# os33_master.net
KiCad netlist of a schematic drawn in EAGLE
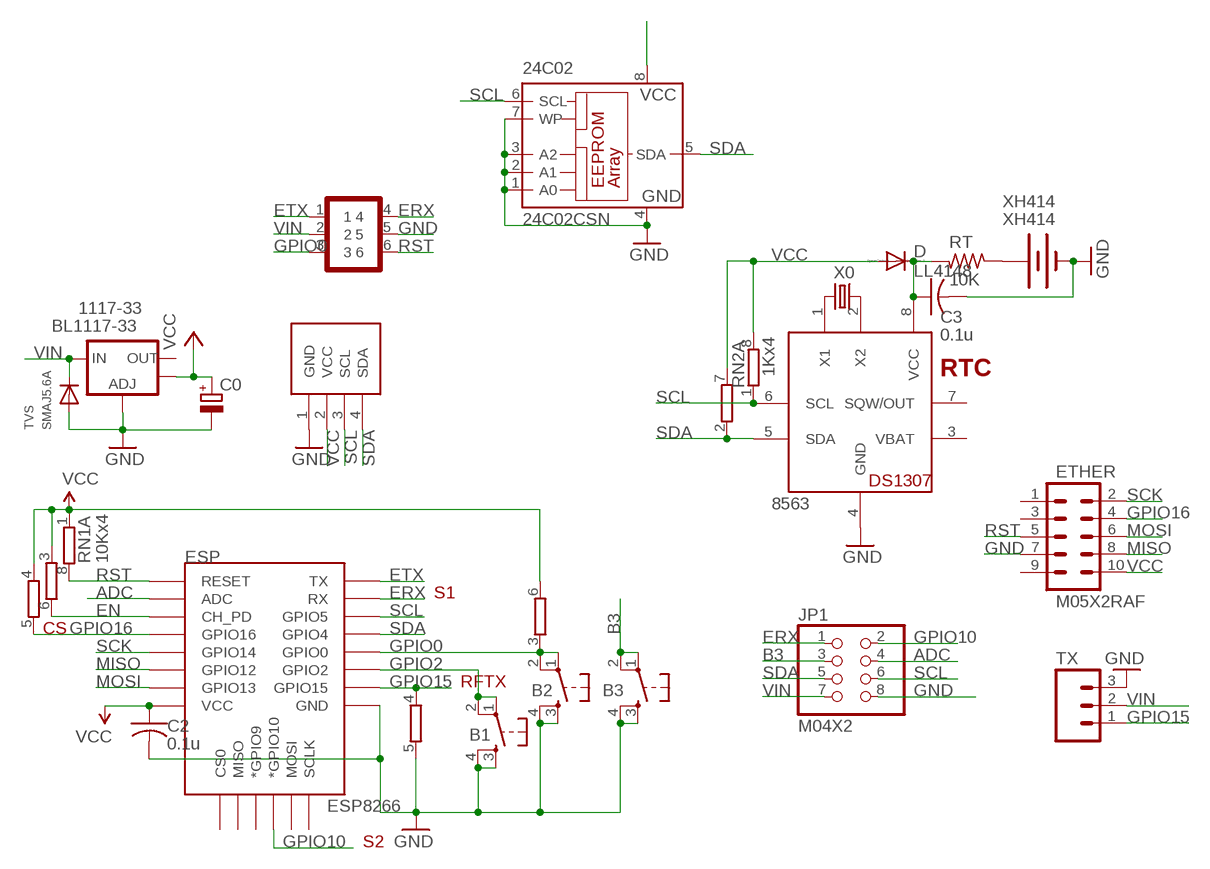
[diagram p0: schematic, sheet 1]

(export (version "E")
  (design (tool "Eeschema 10.0.6"))
  (components
    (comp (ref "24C02")
      (value "24C02CSN")
      (footprint "eagle-import:SO-08")
      (fields (field (name "MF") "MICROCHIP") (field (name "MPN") "24C02C/SN"))
      (libsource (lib "eagle-import") (part "24CSN02C"))
    )
    (comp (ref "1117-33")
      (value "BL1117-33")
      (footprint "eagle-import:SOT223")
      (libsource (lib "eagle-import") (part "V_REG_LM1117SOT223"))
    )
    (comp (ref "8563")
      (value "PCF8563")
      (footprint "eagle-import:SO08")
      (libsource (lib "eagle-import") (part "DS1307SOIC"))
    )
    (comp (ref "B1")
      (value "SPST_TACTEVQQ2")
      (footprint "eagle-import:EVQ-Q2")
      (libsource (lib "eagle-import") (part "SPST_TACTEVQQ2"))
    )
    (comp (ref "B2")
      (value "SPST_TACTEVQQ2")
      (footprint "eagle-import:EVQ-Q2")
      (libsource (lib "eagle-import") (part "SPST_TACTEVQQ2"))
    )
    (comp (ref "B3")
      (value "SPST_TACTEVQQ2")
      (footprint "eagle-import:EVQ-Q2")
      (libsource (lib "eagle-import") (part "SPST_TACTEVQQ2"))
    )
    (comp (ref "C0")
      (value "CPOL-EUC")
      (footprint "eagle-import:PANASONIC_C")
      (libsource (lib "eagle-import") (part "CPOL-EUC"))
    )
    (comp (ref "C2")
      (value "0.1u")
      (footprint "eagle-import:C0603")
      (libsource (lib "eagle-import") (part "C-USC0603"))
    )
    (comp (ref "C3")
      (value "0.1u")
      (footprint "eagle-import:C0603")
      (libsource (lib "eagle-import") (part "C-USC0603"))
    )
    (comp (ref "D")
      (value "LL4148")
      (footprint "eagle-import:MINIMELF")
      (libsource (lib "eagle-import") (part "DIODE-MINIMELF"))
    )
    (comp (ref "ESP")
      (value "ESP8266")
      (footprint "eagle-import:ESP12E-SMD")
      (libsource (lib "eagle-import") (part "ESP12ESMD"))
    )
    (comp (ref "ETHER")
      (value "M05X2RAF")
      (footprint "eagle-import:2X5-RAF")
      (libsource (lib "eagle-import") (part "M05X2RAF"))
    )
    (comp (ref "JP1")
      (value "M04X2")
      (footprint "eagle-import:2X04")
      (libsource (lib "eagle-import") (part "PINHD-2X4"))
    )
    (comp (ref "LCD")
      (value "SSD1306_OLED_I2CPCB0.75BB")
      (footprint "eagle-import:SSD1306_OLED_I2C_PCB_0.75BB")
      (libsource (lib "eagle-import") (part "SSD1306_OLED_I2CPCB0.75BB"))
    )
    (comp (ref "RN1")
      (value "10Kx4")
      (footprint "eagle-import:EXB38V")
      (libsource (lib "eagle-import") (part "4R-NEXB38V"))
    )
    (comp (ref "RN2")
      (value "1Kx4")
      (footprint "eagle-import:EXB38V")
      (libsource (lib "eagle-import") (part "4R-NEXB38V"))
    )
    (comp (ref "RT")
      (value "10K")
      (footprint "eagle-import:R0603")
      (libsource (lib "eagle-import") (part "R-US_R0603"))
    )
    (comp (ref "TVS")
      (value "SMAJ5.6A")
      (footprint "eagle-import:SMADIODE")
      (libsource (lib "eagle-import") (part "DIODESMA"))
    )
    (comp (ref "TX")
      (value "M03LOCK")
      (footprint "eagle-import:1X03_LOCK")
      (libsource (lib "eagle-import") (part "M03LOCK"))
    )
    (comp (ref "U$3")
      (value "GOLDFINGER_2X3")
      (footprint "eagle-import:GOLDFINGER_2X3")
      (libsource (lib "eagle-import") (part "GOLDFINGER_2X3"))
    )
    (comp (ref "X0")
      (value "32.768kHz")
      (footprint "eagle-import:TC26H")
      (libsource (lib "eagle-import") (part "CRYSTALTC26H"))
    )
    (comp (ref "XH414")
      (value "XH414")
      (footprint "eagle-import:BATTCON_XH414")
      (libsource (lib "eagle-import") (part "BATTERYXH414"))
    )
  )
  (nets
    (net (code "1") (name "/ADC") (class "Default")
      (node (ref "ESP") (pin "ADC") (pinfunction "ADC_ADC") (pintype "bidirectional"))
      (node (ref "JP1") (pin "4") (pinfunction "4_4") (pintype "passive"))
    )
    (net (code "2") (name "/B3") (class "Default")
      (node (ref "B3") (pin "1") (pinfunction "1_1") (pintype "passive"))
      (node (ref "B3") (pin "2") (pinfunction "2_2") (pintype "passive"))
      (node (ref "JP1") (pin "3") (pinfunction "3_3") (pintype "passive"))
    )
    (net (code "3") (name "/EN") (class "Default")
      (node (ref "ESP") (pin "CH_PD") (pinfunction "CH_PD_CH_PD") (pintype "bidirectional"))
      (node (ref "RN1") (pin "6") (pinfunction "2_6") (pintype "passive"))
    )
    (net (code "4") (name "/ERX") (class "Default")
      (node (ref "ESP") (pin "RXD0") (pinfunction "RX_RXD0") (pintype "bidirectional"))
      (node (ref "JP1") (pin "1") (pinfunction "1_1") (pintype "passive"))
      (node (ref "U$3") (pin "4") (pinfunction "4_4") (pintype "bidirectional"))
    )
    (net (code "5") (name "/ETX") (class "Default")
      (node (ref "ESP") (pin "TXD0") (pinfunction "TX_TXD0") (pintype "bidirectional"))
      (node (ref "U$3") (pin "1") (pinfunction "1_1") (pintype "bidirectional"))
    )
    (net (code "6") (name "/GPIO0") (class "Default")
      (node (ref "B2") (pin "1") (pinfunction "1_1") (pintype "passive"))
      (node (ref "B2") (pin "2") (pinfunction "2_2") (pintype "passive"))
      (node (ref "ESP") (pin "GPIO0") (pinfunction "GPIO0_GPIO0") (pintype "bidirectional"))
      (node (ref "RN2") (pin "3") (pinfunction "1_3") (pintype "passive"))
      (node (ref "U$3") (pin "3") (pinfunction "3_3") (pintype "bidirectional"))
    )
    (net (code "7") (name "/GPIO2") (class "Default")
      (node (ref "B1") (pin "1") (pinfunction "1_1") (pintype "passive"))
      (node (ref "B1") (pin "2") (pinfunction "2_2") (pintype "passive"))
      (node (ref "ESP") (pin "GPIO2") (pinfunction "GPIO2_GPIO2") (pintype "bidirectional"))
    )
    (net (code "8") (name "/GPIO10") (class "Default")
      (node (ref "ESP") (pin "GPIO10") (pinfunction "*GPIO10_GPIO10") (pintype "bidirectional"))
      (node (ref "JP1") (pin "2") (pinfunction "2_2") (pintype "passive"))
    )
    (net (code "9") (name "/GPIO15") (class "Default")
      (node (ref "ESP") (pin "GPIO15") (pinfunction "GPIO15_GPIO15") (pintype "bidirectional"))
      (node (ref "RN2") (pin "4") (pinfunction "1_4") (pintype "passive"))
      (node (ref "TX") (pin "1") (pinfunction "1_1") (pintype "passive"))
    )
    (net (code "10") (name "/GPIO16") (class "Default")
      (node (ref "ESP") (pin "GPIO16") (pinfunction "GPIO16_GPIO16") (pintype "bidirectional"))
      (node (ref "ETHER") (pin "4") (pinfunction "4_4") (pintype "passive"))
      (node (ref "RN1") (pin "5") (pinfunction "2_5") (pintype "passive"))
    )
    (net (code "11") (name "/MISO") (class "Default")
      (node (ref "ESP") (pin "GPIO12") (pinfunction "GPIO12_GPIO12") (pintype "bidirectional"))
      (node (ref "ETHER") (pin "8") (pinfunction "8_8") (pintype "passive"))
    )
    (net (code "12") (name "/MOSI") (class "Default")
      (node (ref "ESP") (pin "GPIO13") (pinfunction "GPIO13_GPIO13") (pintype "bidirectional"))
      (node (ref "ETHER") (pin "6") (pinfunction "6_6") (pintype "passive"))
    )
    (net (code "13") (name "/RST") (class "Default")
      (node (ref "ESP") (pin "RESET") (pinfunction "RESET_RESET") (pintype "bidirectional"))
      (node (ref "ETHER") (pin "5") (pinfunction "5_5") (pintype "passive"))
      (node (ref "RN1") (pin "8") (pinfunction "2_8") (pintype "passive"))
      (node (ref "U$3") (pin "6") (pinfunction "6_6") (pintype "bidirectional"))
    )
    (net (code "14") (name "/SCK") (class "Default")
      (node (ref "ESP") (pin "GPIO14") (pinfunction "GPIO14_GPIO14") (pintype "bidirectional"))
      (node (ref "ETHER") (pin "2") (pinfunction "2_2") (pintype "passive"))
    )
    (net (code "15") (name "/SCL") (class "Default")
      (node (ref "24C02") (pin "6") (pinfunction "SCL_6") (pintype "input"))
      (node (ref "8563") (pin "6") (pinfunction "SCL_6") (pintype "bidirectional"))
      (node (ref "ESP") (pin "GPIO5") (pinfunction "GPIO5_GPIO5") (pintype "bidirectional"))
      (node (ref "JP1") (pin "6") (pinfunction "6_6") (pintype "passive"))
      (node (ref "LCD") (pin "3") (pinfunction "SCL_3") (pintype "bidirectional"))
      (node (ref "RN2") (pin "1") (pinfunction "1_1") (pintype "passive"))
    )
    (net (code "16") (name "/SDA") (class "Default")
      (node (ref "24C02") (pin "5") (pinfunction "SDA_5") (pintype "bidirectional"))
      (node (ref "8563") (pin "5") (pinfunction "SDA_5") (pintype "bidirectional"))
      (node (ref "ESP") (pin "GPIO4") (pinfunction "GPIO4_GPIO4") (pintype "bidirectional"))
      (node (ref "JP1") (pin "5") (pinfunction "5_5") (pintype "passive"))
      (node (ref "LCD") (pin "4") (pinfunction "SDA_4") (pintype "bidirectional"))
      (node (ref "RN2") (pin "2") (pinfunction "1_2") (pintype "passive"))
    )
    (net (code "17") (name "/VBAT") (class "Default")
      (node (ref "8563") (pin "3") (pinfunction "VBAT_3") (pintype "power_in"))
    )
    (net (code "18") (name "/VIN") (class "Default")
      (node (ref "1117-33") (pin "3") (pinfunction "IN_3") (pintype "input"))
      (node (ref "JP1") (pin "7") (pinfunction "7_7") (pintype "passive"))
      (node (ref "TVS") (pin "C") (pinfunction "C_C") (pintype "passive"))
      (node (ref "TX") (pin "2") (pinfunction "2_2") (pintype "passive"))
      (node (ref "U$3") (pin "2") (pinfunction "2_2") (pintype "bidirectional"))
    )
    (net (code "19") (name "GND") (class "Default")
      (node (ref "1117-33") (pin "1") (pinfunction "ADJ_1") (pintype "input"))
      (node (ref "24C02") (pin "1") (pinfunction "A0_1") (pintype "input"))
      (node (ref "24C02") (pin "2") (pinfunction "A1_2") (pintype "input"))
      (node (ref "24C02") (pin "3") (pinfunction "A2_3") (pintype "input"))
      (node (ref "24C02") (pin "4") (pinfunction "GND_4") (pintype "power_in"))
      (node (ref "24C02") (pin "7") (pinfunction "WP_7") (pintype "input"))
      (node (ref "8563") (pin "4") (pinfunction "GND_4") (pintype "power_in"))
      (node (ref "B1") (pin "3") (pinfunction "3_3") (pintype "passive"))
      (node (ref "B1") (pin "4") (pinfunction "4_4") (pintype "passive"))
      (node (ref "B2") (pin "3") (pinfunction "3_3") (pintype "passive"))
      (node (ref "B2") (pin "4") (pinfunction "4_4") (pintype "passive"))
      (node (ref "B3") (pin "3") (pinfunction "3_3") (pintype "passive"))
      (node (ref "B3") (pin "4") (pinfunction "4_4") (pintype "passive"))
      (node (ref "C0") (pin "-") (pinfunction "-_-") (pintype "passive"))
      (node (ref "C2") (pin "2") (pinfunction "2_2") (pintype "passive"))
      (node (ref "C3") (pin "2") (pinfunction "2_2") (pintype "passive"))
      (node (ref "ESP") (pin "GND") (pinfunction "GND_GND") (pintype "bidirectional"))
      (node (ref "ETHER") (pin "7") (pinfunction "7_7") (pintype "passive"))
      (node (ref "JP1") (pin "8") (pinfunction "8_8") (pintype "passive"))
      (node (ref "LCD") (pin "1") (pinfunction "GND_1") (pintype "power_in"))
      (node (ref "RN2") (pin "5") (pinfunction "2_5") (pintype "passive"))
      (node (ref "TVS") (pin "A") (pinfunction "A_A") (pintype "passive"))
      (node (ref "TX") (pin "3") (pinfunction "3_3") (pintype "passive"))
      (node (ref "U$3") (pin "5") (pinfunction "5_5") (pintype "bidirectional"))
      (node (ref "XH414") (pin "P$1") (pinfunction "-_P$1") (pintype "power_in"))
    )
    (net (code "20") (name "Net-(8563-VCC)") (class "Default")
      (node (ref "8563") (pin "8") (pinfunction "VCC_8") (pintype "power_in"))
      (node (ref "C3") (pin "1") (pinfunction "1_1") (pintype "passive"))
      (node (ref "D") (pin "C") (pinfunction "C_C") (pintype "passive"))
      (node (ref "RT") (pin "2") (pinfunction "2_2") (pintype "passive"))
    )
    (net (code "21") (name "Net-(8563-X1)") (class "Default")
      (node (ref "8563") (pin "1") (pinfunction "X1_1") (pintype "passive"))
      (node (ref "X0") (pin "2") (pinfunction "2_2") (pintype "passive"))
    )
    (net (code "22") (name "Net-(8563-X2)") (class "Default")
      (node (ref "8563") (pin "2") (pinfunction "X2_2") (pintype "passive"))
      (node (ref "X0") (pin "1") (pinfunction "1_1") (pintype "passive"))
    )
    (net (code "23") (name "Net-(XH414-+)") (class "Default")
      (node (ref "RT") (pin "1") (pinfunction "1_1") (pintype "passive"))
      (node (ref "XH414") (pin "P$2") (pinfunction "+_P$2") (pintype "power_in"))
    )
    (net (code "24") (name "VCC") (class "Default")
      (node (ref "1117-33") (pin "4") (pinfunction "OUT_4") (pintype "bidirectional"))
      (node (ref "24C02") (pin "8") (pinfunction "VCC_8") (pintype "power_in"))
      (node (ref "C0") (pin "+") (pinfunction "+_+") (pintype "passive"))
      (node (ref "C2") (pin "1") (pinfunction "1_1") (pintype "passive"))
      (node (ref "D") (pin "A") (pinfunction "A_A") (pintype "passive"))
      (node (ref "ESP") (pin "VCC") (pinfunction "VCC_VCC") (pintype "bidirectional"))
      (node (ref "ETHER") (pin "10") (pinfunction "10_10") (pintype "passive"))
      (node (ref "LCD") (pin "2") (pinfunction "VCC_2") (pintype "power_in"))
      (node (ref "RN1") (pin "1") (pinfunction "1_1") (pintype "passive"))
      (node (ref "RN1") (pin "3") (pinfunction "1_3") (pintype "passive"))
      (node (ref "RN1") (pin "4") (pinfunction "1_4") (pintype "passive"))
      (node (ref "RN2") (pin "6") (pinfunction "2_6") (pintype "passive"))
      (node (ref "RN2") (pin "7") (pinfunction "2_7") (pintype "passive"))
      (node (ref "RN2") (pin "8") (pinfunction "2_8") (pintype "passive"))
    )
    (net (code "25") (name "unconnected-(1117-33-OUT-Pad2)") (class "Default")
      (node (ref "1117-33") (pin "2") (pinfunction "OUT_2") (pintype "bidirectional"))
    )
    (net (code "26") (name "unconnected-(8563-SQW{slash}OUT-Pad7)") (class "Default")
      (node (ref "8563") (pin "7") (pinfunction "SQW/OUT_7") (pintype "bidirectional"))
    )
    (net (code "27") (name "unconnected-(ESP-*GPIO9-PadGPIO9)") (class "Default")
      (node (ref "ESP") (pin "GPIO9") (pinfunction "*GPIO9_GPIO9") (pintype "bidirectional"))
    )
    (net (code "28") (name "unconnected-(ESP-PadCS0)") (class "Default")
      (node (ref "ESP") (pin "CS0") (pinfunction "CS0_CS0") (pintype "bidirectional"))
    )
    (net (code "29") (name "unconnected-(ESP-PadMISO)") (class "Default")
      (node (ref "ESP") (pin "MISO") (pinfunction "MISO_MISO") (pintype "bidirectional"))
    )
    (net (code "30") (name "unconnected-(ESP-PadMOSI)") (class "Default")
      (node (ref "ESP") (pin "MOSI") (pinfunction "MOSI_MOSI") (pintype "bidirectional"))
    )
    (net (code "31") (name "unconnected-(ESP-PadSCLK)") (class "Default")
      (node (ref "ESP") (pin "SCLK") (pinfunction "SCLK_SCLK") (pintype "bidirectional"))
    )
    (net (code "32") (name "unconnected-(ETHER-Pad1)") (class "Default")
      (node (ref "ETHER") (pin "1") (pinfunction "1_1") (pintype "passive"))
    )
    (net (code "33") (name "unconnected-(ETHER-Pad3)") (class "Default")
      (node (ref "ETHER") (pin "3") (pinfunction "3_3") (pintype "passive"))
    )
    (net (code "34") (name "unconnected-(ETHER-Pad9)") (class "Default")
      (node (ref "ETHER") (pin "9") (pinfunction "9_9") (pintype "passive"))
    )
  )
)
